# mr_radar_pulser.net
KiCad netlist of a schematic drawn in EAGLE
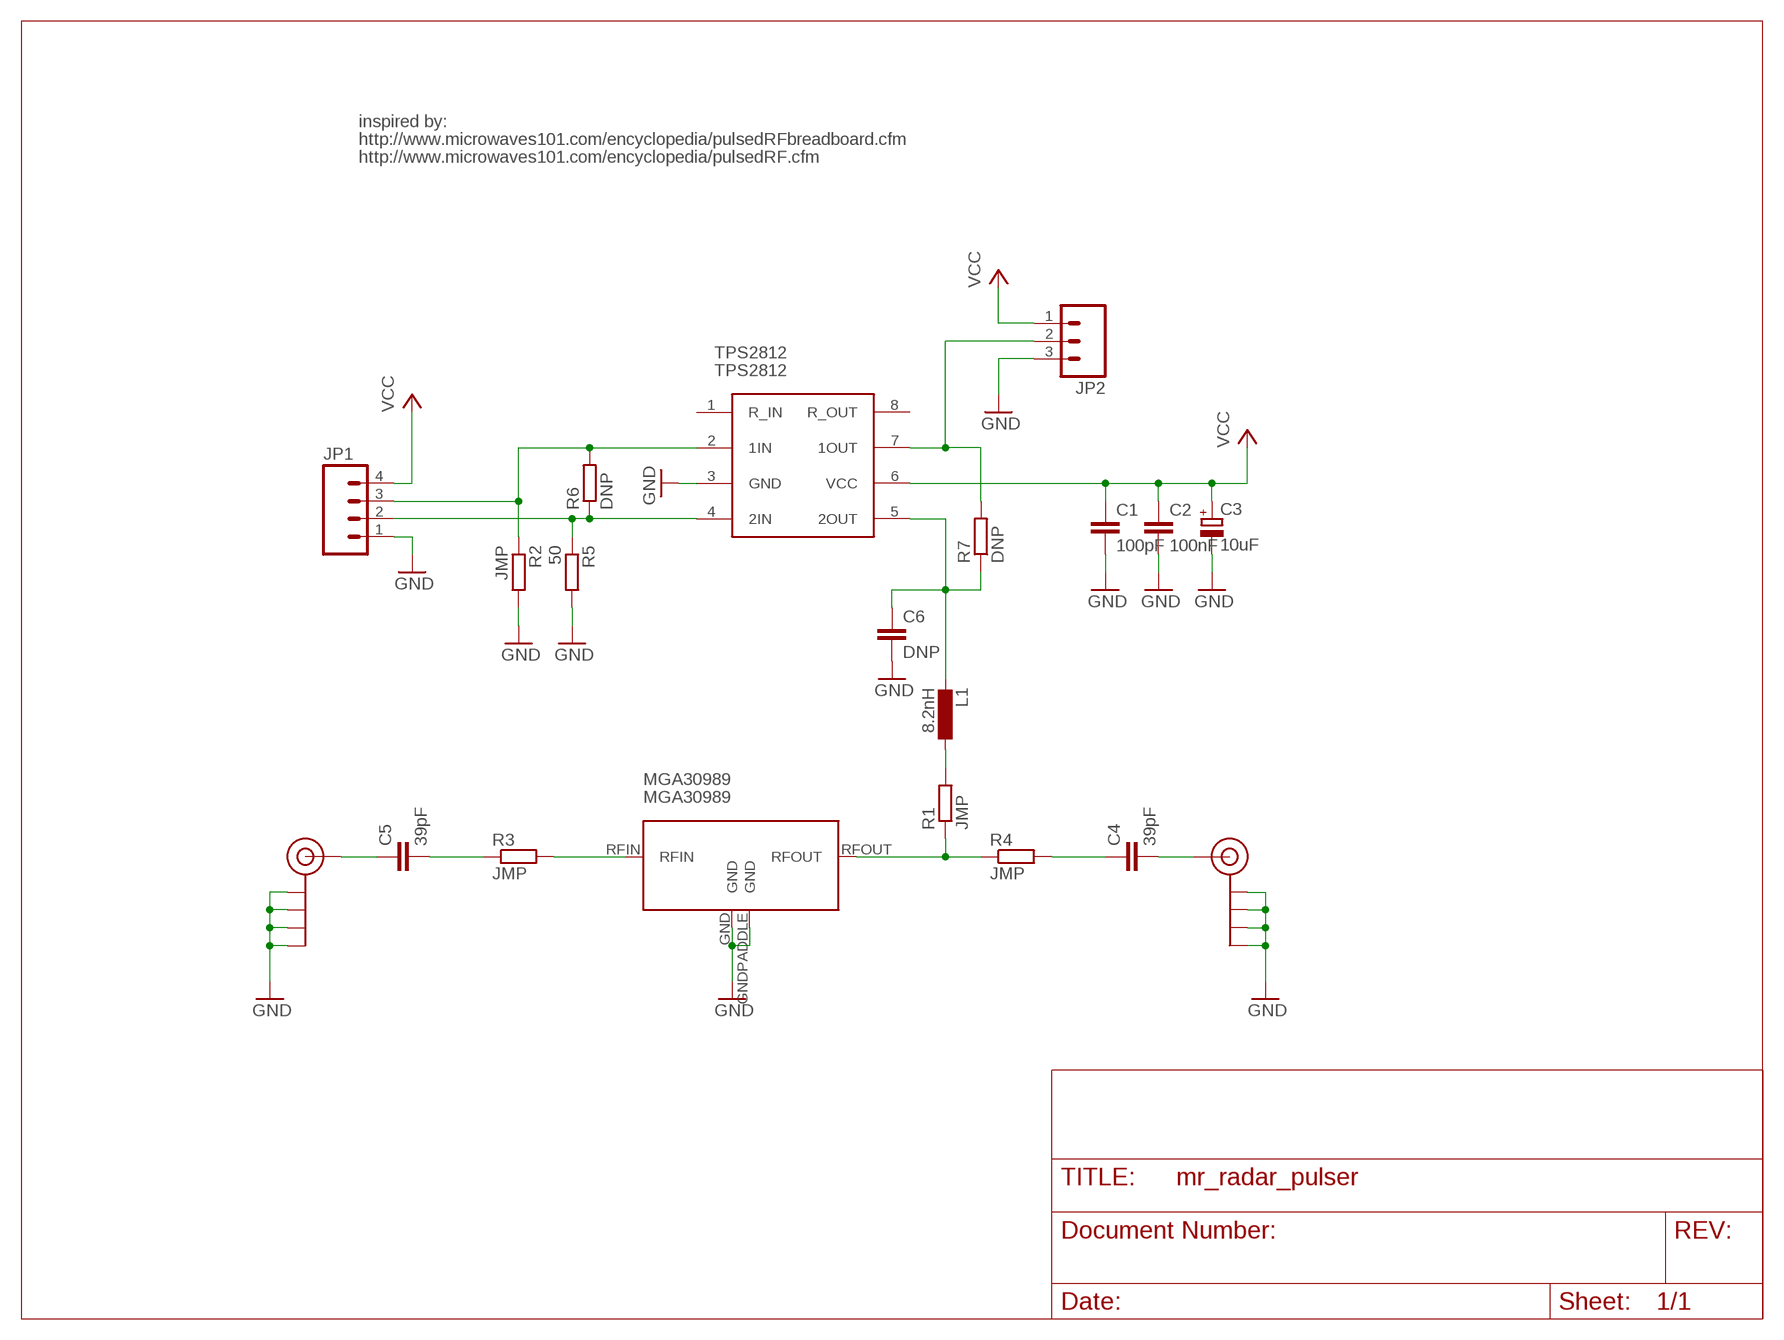
[diagram p0: schematic, sheet 1]

(export (version "E")
  (design (tool "Eeschema 10.0.6"))
  (components
    (comp (ref "C1")
      (value "100pF")
      (footprint "eagle-import:C0603")
      (libsource (lib "eagle-import") (part "C-EUC0603"))
    )
    (comp (ref "C2")
      (value "100nF")
      (footprint "eagle-import:C0603")
      (libsource (lib "eagle-import") (part "C-EUC0603"))
    )
    (comp (ref "C3")
      (value "10uF")
      (footprint "eagle-import:CT3216")
      (libsource (lib "eagle-import") (part "CPOL-EUCT3216"))
    )
    (comp (ref "C4")
      (value "39pF")
      (footprint "eagle-import:C0402")
      (libsource (lib "eagle-import") (part "C-EUC0402"))
    )
    (comp (ref "C5")
      (value "39pF")
      (footprint "eagle-import:C0402")
      (libsource (lib "eagle-import") (part "C-EUC0402"))
    )
    (comp (ref "C6")
      (value "DNP")
      (footprint "eagle-import:C0603")
      (libsource (lib "eagle-import") (part "C-EUC0603"))
    )
    (comp (ref "J$1")
      (value "SMA_EDGE")
      (footprint "eagle-import:SMA-EDGE")
      (libsource (lib "eagle-import") (part "SMA_EDGE"))
    )
    (comp (ref "J$2")
      (value "SMA_EDGE")
      (footprint "eagle-import:SMA-EDGE")
      (libsource (lib "eagle-import") (part "SMA_EDGE"))
    )
    (comp (ref "JP1")
      (value "M04PTH")
      (footprint "eagle-import:1X04")
      (libsource (lib "eagle-import") (part "M04PTH"))
    )
    (comp (ref "JP2")
      (value "M03PTH")
      (footprint "eagle-import:1X03")
      (libsource (lib "eagle-import") (part "M03PTH"))
    )
    (comp (ref "L1")
      (value "8.2nH")
      (footprint "eagle-import:0603-IND")
      (libsource (lib "eagle-import") (part "INDUCTOR-0603"))
    )
    (comp (ref "MGA30989")
      (value "MGA30989")
      (footprint "eagle-import:SOT89")
      (libsource (lib "eagle-import") (part "MGA30989"))
    )
    (comp (ref "R1")
      (value "JMP")
      (footprint "eagle-import:R0603")
      (libsource (lib "eagle-import") (part "R-EU_R0603"))
    )
    (comp (ref "R2")
      (value "JMP")
      (footprint "eagle-import:R0603")
      (libsource (lib "eagle-import") (part "R-EU_R0603"))
    )
    (comp (ref "R3")
      (value "JMP")
      (footprint "eagle-import:R0402")
      (libsource (lib "eagle-import") (part "R-EU_R0402"))
    )
    (comp (ref "R4")
      (value "JMP")
      (footprint "eagle-import:R0402")
      (libsource (lib "eagle-import") (part "R-EU_R0402"))
    )
    (comp (ref "R5")
      (value "50")
      (footprint "eagle-import:R0603")
      (libsource (lib "eagle-import") (part "R-EU_R0603"))
    )
    (comp (ref "R6")
      (value "DNP")
      (footprint "eagle-import:R0603")
      (libsource (lib "eagle-import") (part "R-EU_R0603"))
    )
    (comp (ref "R7")
      (value "DNP")
      (footprint "eagle-import:R0603")
      (libsource (lib "eagle-import") (part "R-EU_R0603"))
    )
    (comp (ref "TPS2812")
      (value "TPS2812")
      (footprint "eagle-import:SO8")
      (libsource (lib "eagle-import") (part "TPS2812"))
    )
  )
  (nets
    (net (code "1") (name "GND") (class "Default")
      (node (ref "C1") (pin "2") (pinfunction "2_2") (pintype "passive"))
      (node (ref "C2") (pin "2") (pinfunction "2_2") (pintype "passive"))
      (node (ref "C3") (pin "-") (pinfunction "-_-") (pintype "passive"))
      (node (ref "C6") (pin "2") (pinfunction "2_2") (pintype "passive"))
      (node (ref "J$1") (pin "GND@0") (pinfunction "GND_GND@0") (pintype "bidirectional"))
      (node (ref "J$1") (pin "GND@1") (pinfunction "GND_GND@1") (pintype "bidirectional"))
      (node (ref "J$1") (pin "GND@2") (pinfunction "GND_GND@2") (pintype "bidirectional"))
      (node (ref "J$1") (pin "GND@3") (pinfunction "GND_GND@3") (pintype "bidirectional"))
      (node (ref "J$2") (pin "GND@0") (pinfunction "GND_GND@0") (pintype "bidirectional"))
      (node (ref "J$2") (pin "GND@1") (pinfunction "GND_GND@1") (pintype "bidirectional"))
      (node (ref "J$2") (pin "GND@2") (pinfunction "GND_GND@2") (pintype "bidirectional"))
      (node (ref "J$2") (pin "GND@3") (pinfunction "GND_GND@3") (pintype "bidirectional"))
      (node (ref "JP1") (pin "1") (pinfunction "1_1") (pintype "passive"))
      (node (ref "JP2") (pin "3") (pinfunction "3_3") (pintype "passive"))
      (node (ref "MGA30989") (pin "GND") (pinfunction "GND_GND") (pintype "power_in"))
      (node (ref "MGA30989") (pin "GNDPADDLE") (pinfunction "GND_GNDPADDLE") (pintype "power_in"))
      (node (ref "R2") (pin "2") (pinfunction "2_2") (pintype "passive"))
      (node (ref "R5") (pin "2") (pinfunction "2_2") (pintype "passive"))
      (node (ref "TPS2812") (pin "3") (pinfunction "GND_3") (pintype "power_in"))
    )
    (net (code "2") (name "Net-(C4-Pad1)") (class "Default")
      (node (ref "C4") (pin "1") (pinfunction "1_1") (pintype "passive"))
      (node (ref "R4") (pin "2") (pinfunction "2_2") (pintype "passive"))
    )
    (net (code "3") (name "Net-(C5-Pad2)") (class "Default")
      (node (ref "C5") (pin "2") (pinfunction "2_2") (pintype "passive"))
      (node (ref "R3") (pin "1") (pinfunction "1_1") (pintype "passive"))
    )
    (net (code "4") (name "Net-(J$1-SIGNAL)") (class "Default")
      (node (ref "C5") (pin "1") (pinfunction "1_1") (pintype "passive"))
      (node (ref "J$1") (pin "SIG") (pinfunction "SIGNAL_SIG") (pintype "bidirectional"))
    )
    (net (code "5") (name "Net-(J$2-SIGNAL)") (class "Default")
      (node (ref "C4") (pin "2") (pinfunction "2_2") (pintype "passive"))
      (node (ref "J$2") (pin "SIG") (pinfunction "SIGNAL_SIG") (pintype "bidirectional"))
    )
    (net (code "6") (name "Net-(L1-1)") (class "Default")
      (node (ref "L1") (pin "P$1") (pinfunction "1_P$1") (pintype "passive"))
      (node (ref "R1") (pin "2") (pinfunction "2_2") (pintype "passive"))
    )
    (net (code "7") (name "Net-(L1-2)") (class "Default")
      (node (ref "C6") (pin "1") (pinfunction "1_1") (pintype "passive"))
      (node (ref "L1") (pin "P$2") (pinfunction "2_P$2") (pintype "passive"))
      (node (ref "R7") (pin "1") (pinfunction "1_1") (pintype "passive"))
      (node (ref "TPS2812") (pin "5") (pinfunction "2OUT_5") (pintype "output"))
    )
    (net (code "8") (name "Net-(MGA30989-PadRFIN)") (class "Default")
      (node (ref "MGA30989") (pin "RFIN") (pinfunction "RFIN_RFIN") (pintype "input"))
      (node (ref "R3") (pin "2") (pinfunction "2_2") (pintype "passive"))
    )
    (net (code "9") (name "Net-(MGA30989-PadRFOUT)") (class "Default")
      (node (ref "MGA30989") (pin "RFOUT") (pinfunction "RFOUT_RFOUT") (pintype "output"))
      (node (ref "R1") (pin "1") (pinfunction "1_1") (pintype "passive"))
      (node (ref "R4") (pin "1") (pinfunction "1_1") (pintype "passive"))
    )
    (net (code "10") (name "Net-(TPS2812-1IN)") (class "Default")
      (node (ref "JP1") (pin "3") (pinfunction "3_3") (pintype "passive"))
      (node (ref "R2") (pin "1") (pinfunction "1_1") (pintype "passive"))
      (node (ref "R6") (pin "2") (pinfunction "2_2") (pintype "passive"))
      (node (ref "TPS2812") (pin "2") (pinfunction "1IN_2") (pintype "input"))
    )
    (net (code "11") (name "Net-(TPS2812-1OUT)") (class "Default")
      (node (ref "JP2") (pin "2") (pinfunction "2_2") (pintype "passive"))
      (node (ref "R7") (pin "2") (pinfunction "2_2") (pintype "passive"))
      (node (ref "TPS2812") (pin "7") (pinfunction "1OUT_7") (pintype "output"))
    )
    (net (code "12") (name "Net-(TPS2812-2IN)") (class "Default")
      (node (ref "JP1") (pin "2") (pinfunction "2_2") (pintype "passive"))
      (node (ref "R5") (pin "1") (pinfunction "1_1") (pintype "passive"))
      (node (ref "R6") (pin "1") (pinfunction "1_1") (pintype "passive"))
      (node (ref "TPS2812") (pin "4") (pinfunction "2IN_4") (pintype "input"))
    )
    (net (code "13") (name "VCC") (class "Default")
      (node (ref "C1") (pin "1") (pinfunction "1_1") (pintype "passive"))
      (node (ref "C2") (pin "1") (pinfunction "1_1") (pintype "passive"))
      (node (ref "C3") (pin "+") (pinfunction "+_+") (pintype "passive"))
      (node (ref "JP1") (pin "4") (pinfunction "4_4") (pintype "passive"))
      (node (ref "JP2") (pin "1") (pinfunction "1_1") (pintype "passive"))
      (node (ref "TPS2812") (pin "6") (pinfunction "VCC_6") (pintype "bidirectional"))
    )
    (net (code "14") (name "unconnected-(TPS2812-R_IN-Pad1)") (class "Default")
      (node (ref "TPS2812") (pin "1") (pinfunction "R_IN_1") (pintype "input"))
    )
    (net (code "15") (name "unconnected-(TPS2812-R_OUT-Pad8)") (class "Default")
      (node (ref "TPS2812") (pin "8") (pinfunction "R_OUT_8") (pintype "output"))
    )
  )
)
